# M5_Stick_LocoNet_Interface_2021-01-25.net
KiCad netlist of a schematic drawn in EasyEDA
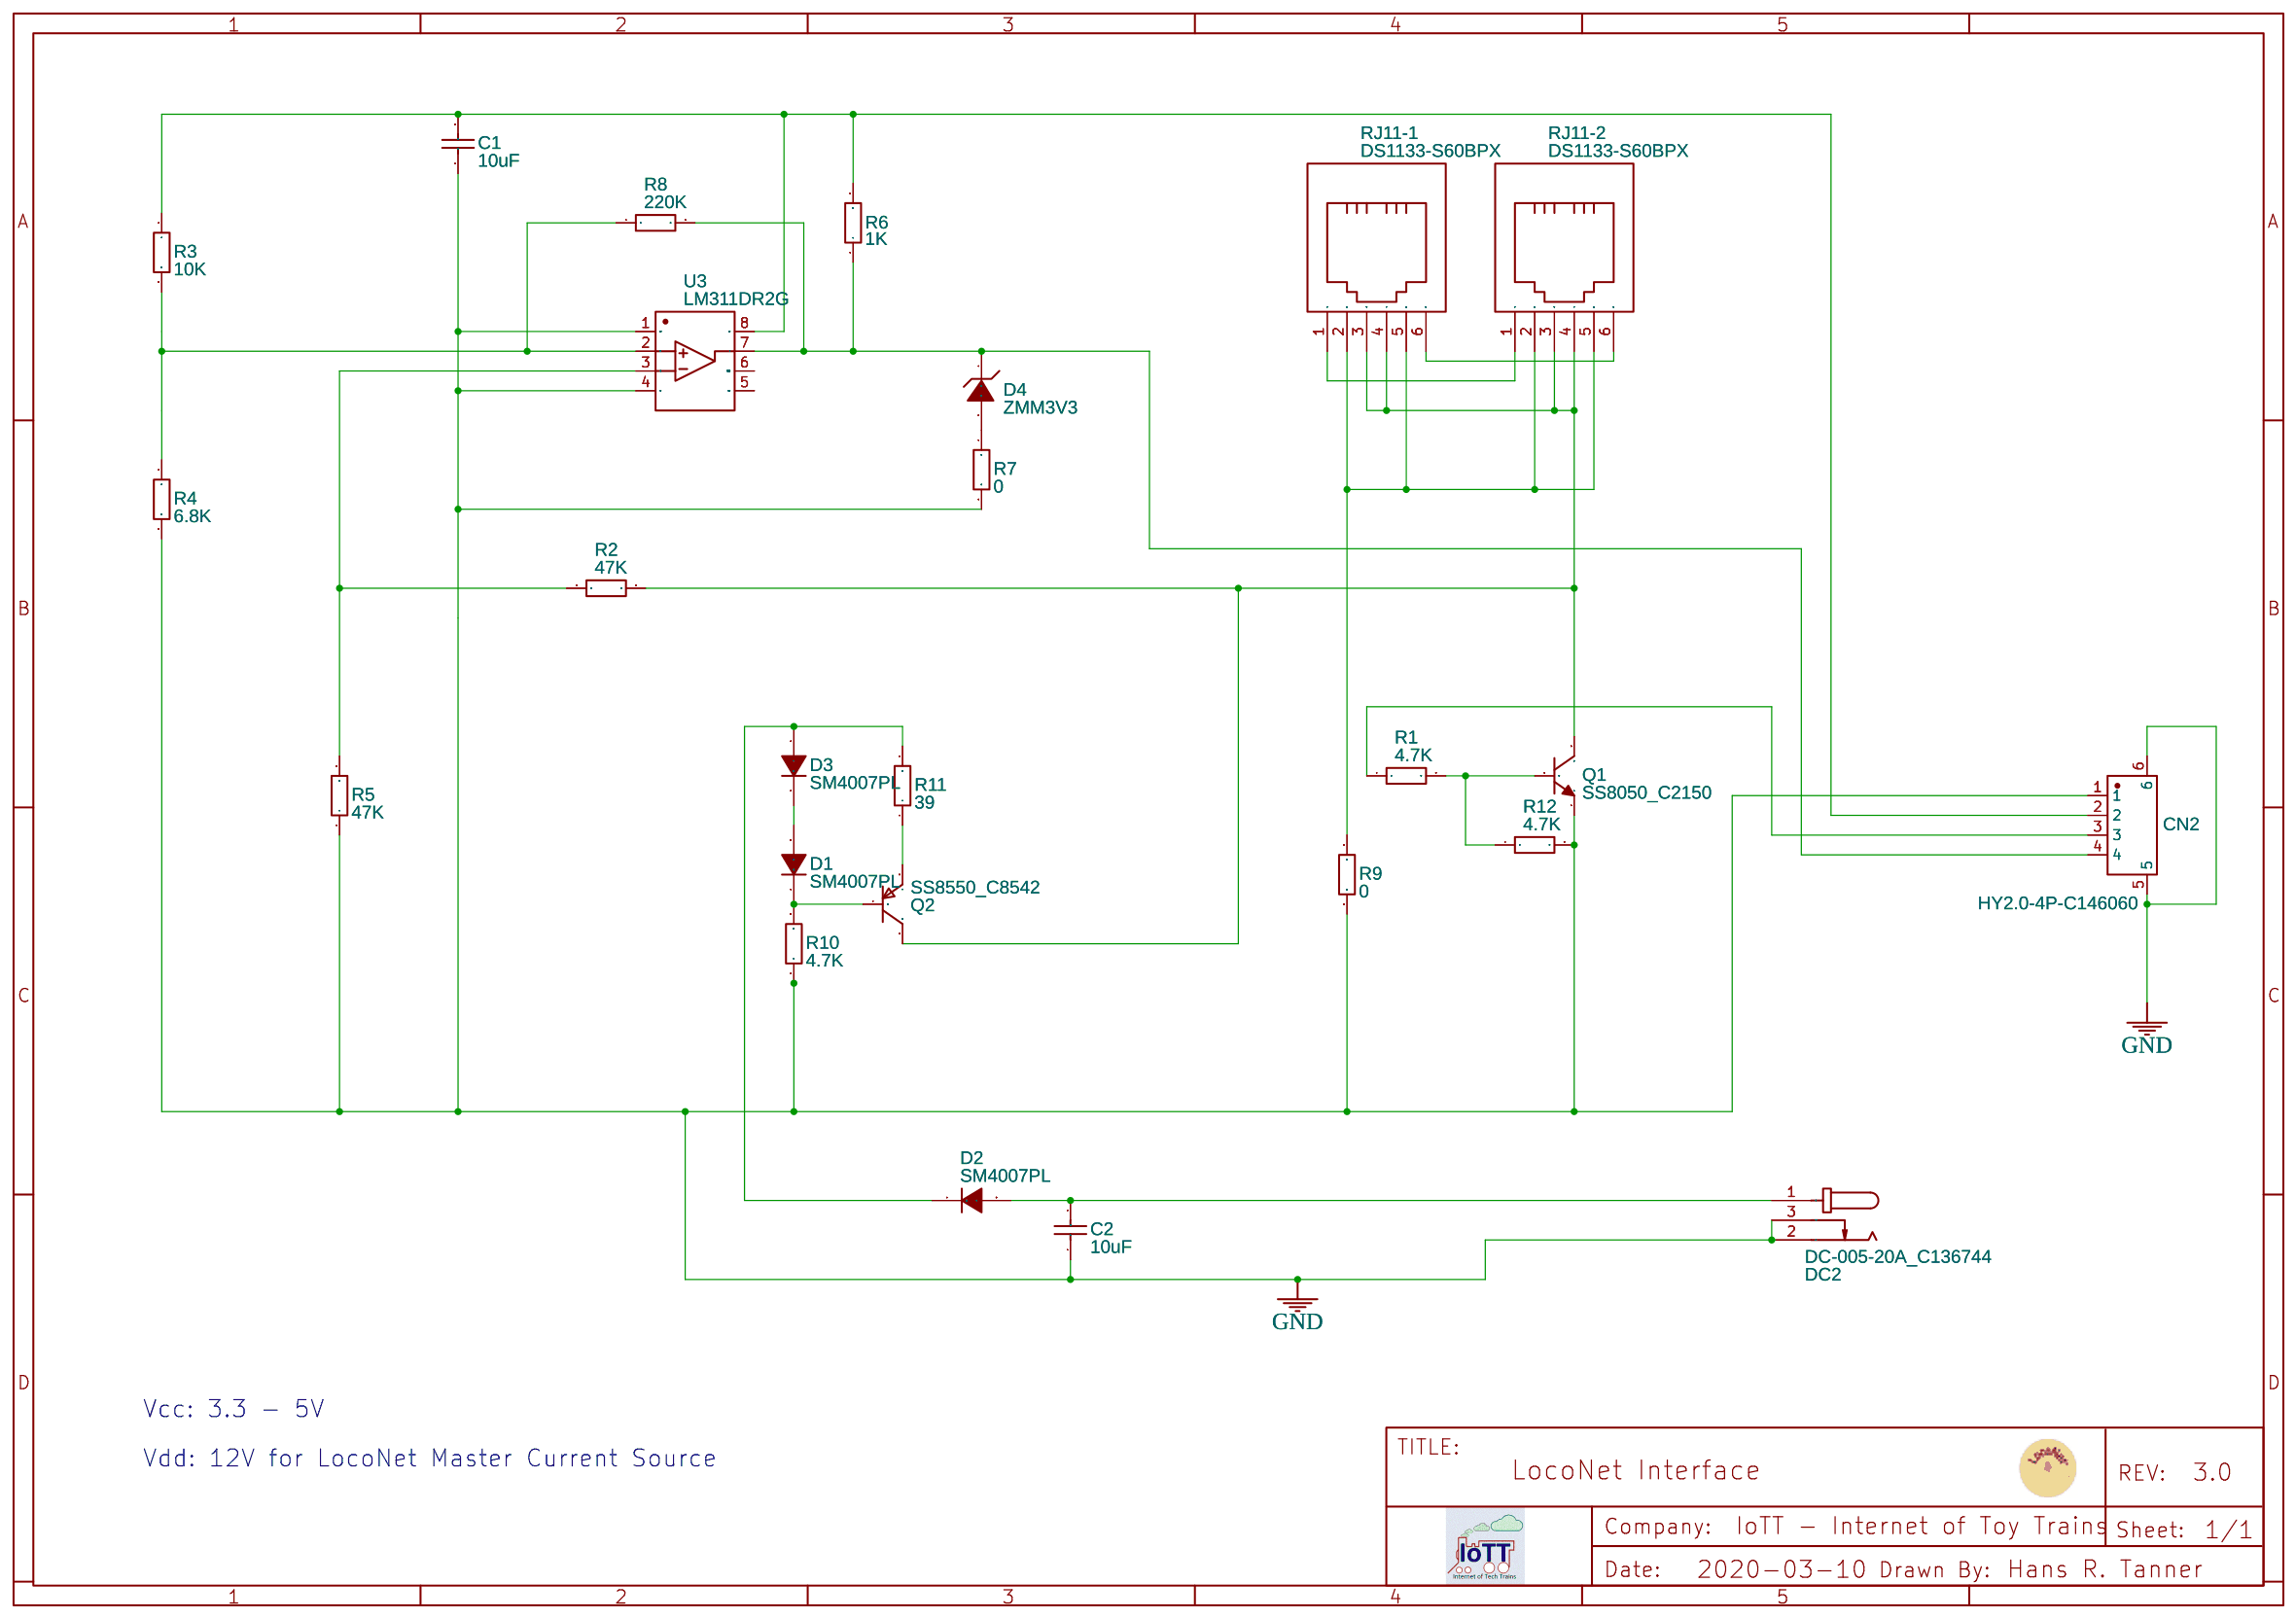
[diagram p0: schematic sheet]

(export (version "E")
  (design (tool "Eeschema 10.0.6"))
  (components
    (comp (ref "C1")
      (value "10uF")
      (fields
        (field (name "BOM_Manufacturer Part") "CL21A106KAYNNNE")
        (field (name "BOM_Supplier Part") "C15850")
      )
      (libsource (lib "") (part "CL21A106KAYNNNE"))
    )
    (comp (ref "C2")
      (value "10uF")
      (fields
        (field (name "BOM_Manufacturer Part") "CL21A106KAYNNNE")
        (field (name "BOM_Supplier Part") "C15850")
      )
      (libsource (lib "") (part "CL21A106KAYNNNE"))
    )
    (comp (ref "CN2")
      (value "HY2.0-4P-C146060")
      (fields (field (name "BOM_Supplier Part") "C146060"))
      (libsource (lib "") (part "HY2.0-4P-C146060"))
    )
    (comp (ref "D1")
      (value "SM4007PL")
      (fields (field (name "BOM_Supplier Part") "C64898"))
      (libsource (lib "") (part "SM4007PL"))
    )
    (comp (ref "D2")
      (value "SM4007PL")
      (fields (field (name "BOM_Supplier Part") "C64898"))
      (libsource (lib "") (part "SM4007PL_1"))
    )
    (comp (ref "D3")
      (value "SM4007PL")
      (fields (field (name "BOM_Supplier Part") "C64898"))
      (libsource (lib "") (part "SM4007PL"))
    )
    (comp (ref "D4")
      (value "ZMM3V3")
      (fields (field (name "BOM_Supplier Part") "C8056"))
      (libsource (lib "") (part "ZMM3V3"))
    )
    (comp (ref "DC2")
      (value "DC-005-20A_C136744")
      (fields
        (field (name "BOM_Manufacturer Part") "DC-005-20A")
        (field (name "BOM_Supplier Part") "C136744")
      )
      (libsource (lib "") (part "DC-005-20A_C136744"))
    )
    (comp (ref "Q1")
      (value "SS8050_C2150")
      (fields (field (name "BOM_Manufacturer Part") "SS8050") (field (name "BOM_Supplier Part") "C2150"))
      (libsource (lib "") (part "SS8050_C2150"))
    )
    (comp (ref "Q2")
      (value "SS8550_C8542")
      (fields (field (name "BOM_Manufacturer Part") "SS8550") (field (name "BOM_Supplier Part") "C8542"))
      (libsource (lib "") (part "SS8550_C8542"))
    )
    (comp (ref "R1")
      (value "4.7K")
      (fields
        (field (name "BOM_Manufacturer Part") "0603WAF4701T5E")
        (field (name "BOM_Supplier Part") "C23162")
      )
      (libsource (lib "") (part "0603WAF4701T5E_1"))
    )
    (comp (ref "R2")
      (value "47K")
      (fields
        (field (name "BOM_Manufacturer Part") "0603WAF4702T5E")
        (field (name "BOM_Supplier Part") "C25819")
      )
      (libsource (lib "") (part "0603WAF4702T5E_1"))
    )
    (comp (ref "R3")
      (value "10K")
      (fields
        (field (name "BOM_Manufacturer Part") "0603WAF1002T5E")
        (field (name "BOM_Supplier Part") "C25804")
      )
      (libsource (lib "") (part "0603WAF1002T5E"))
    )
    (comp (ref "R4")
      (value "6.8K")
      (fields
        (field (name "BOM_Manufacturer Part") "0603WAF6801T5E")
        (field (name "BOM_Supplier Part") "C23212")
      )
      (libsource (lib "") (part "0603WAF6801T5E"))
    )
    (comp (ref "R5")
      (value "47K")
      (fields
        (field (name "BOM_Manufacturer Part") "0603WAF4702T5E")
        (field (name "BOM_Supplier Part") "C25819")
      )
      (libsource (lib "") (part "0603WAF4702T5E"))
    )
    (comp (ref "R6")
      (value "1K")
      (fields
        (field (name "BOM_Manufacturer Part") "0402WGF1001TCE")
        (field (name "BOM_Supplier Part") "C11702")
      )
      (libsource (lib "") (part "0402WGF1001TCE"))
    )
    (comp (ref "R7")
      (value "0")
      (fields
        (field (name "BOM_Manufacturer Part") "0402WGF0000TCE")
        (field (name "BOM_Supplier Part") "C17168")
      )
      (libsource (lib "") (part "0402WGF0000TCE"))
    )
    (comp (ref "R8")
      (value "220K")
      (fields
        (field (name "BOM_Manufacturer Part") "0603WAF2203T5E")
        (field (name "BOM_Supplier Part") "C22961")
      )
      (libsource (lib "") (part "0603WAF2203T5E"))
    )
    (comp (ref "R9")
      (value "0")
      (fields
        (field (name "BOM_Manufacturer Part") "0402WGF0000TCE")
        (field (name "BOM_Supplier Part") "C17168")
      )
      (libsource (lib "") (part "0402WGF0000TCE"))
    )
    (comp (ref "R10")
      (value "4.7K")
      (fields
        (field (name "BOM_Manufacturer Part") "0603WAF4701T5E")
        (field (name "BOM_Supplier Part") "C23162")
      )
      (libsource (lib "") (part "0603WAF4701T5E"))
    )
    (comp (ref "R11")
      (value "39")
      (fields
        (field (name "BOM_Manufacturer Part") "TC0325B390JT5E")
        (field (name "BOM_Supplier Part") "C146566")
      )
      (libsource (lib "") (part "TC0325B390JT5E"))
    )
    (comp (ref "R12")
      (value "4.7K")
      (fields
        (field (name "BOM_Manufacturer Part") "0603WAF4701T5E")
        (field (name "BOM_Supplier Part") "C23162")
      )
      (libsource (lib "") (part "0603WAF4701T5E_1"))
    )
    (comp (ref "RJ11-1")
      (value "DS1133-S60BPX")
      (fields (field (name "BOM_Supplier Part") "C77859"))
      (libsource (lib "") (part "Unknown_690_-680"))
    )
    (comp (ref "RJ11-2")
      (value "DS1133-S60BPX")
      (fields (field (name "BOM_Supplier Part") "C77859"))
      (libsource (lib "") (part "Unknown_785_-680"))
    )
    (comp (ref "U3")
      (value "LM311DR2G")
      (fields (field (name "BOM_Supplier Part") "C231850"))
      (libsource (lib "") (part "LM311DR2G"))
    )
  )
  (nets
    (net (code "1") (name "GND") (class "Default")
      (node (ref "C1") (pin "1") (pinfunction "1_1") (pintype "input"))
      (node (ref "C2") (pin "1") (pinfunction "1_1") (pintype "input"))
      (node (ref "CN2") (pin "1") (pinfunction "1_1") (pintype "unspecified"))
      (node (ref "CN2") (pin "5") (pinfunction "5_5") (pintype "unspecified"))
      (node (ref "CN2") (pin "6") (pinfunction "6_6") (pintype "unspecified"))
      (node (ref "DC2") (pin "2") (pinfunction "2_2") (pintype "unspecified"))
      (node (ref "DC2") (pin "3") (pinfunction "3_3") (pintype "unspecified"))
      (node (ref "Q1") (pin "2") (pinfunction "E_2") (pintype "unspecified"))
      (node (ref "R10") (pin "1") (pinfunction "1_1") (pintype "input"))
      (node (ref "R12") (pin "2") (pinfunction "2_2") (pintype "input"))
      (node (ref "R4") (pin "2") (pinfunction "2_2") (pintype "input"))
      (node (ref "R5") (pin "1") (pinfunction "1_1") (pintype "input"))
      (node (ref "R7") (pin "2") (pinfunction "2_2") (pintype "input"))
      (node (ref "R9") (pin "2") (pinfunction "2_2") (pintype "input"))
      (node (ref "U3") (pin "1") (pinfunction "GND_1") (pintype "unspecified"))
      (node (ref "U3") (pin "4") (pinfunction "VEE_4") (pintype "unspecified"))
    )
    (net (code "2") (name "Net-(CN2-Pad3)") (class "Default")
      (node (ref "CN2") (pin "3") (pinfunction "3_3") (pintype "unspecified"))
      (node (ref "R1") (pin "1") (pinfunction "1_1") (pintype "input"))
    )
    (net (code "3") (name "Net-(D1-A)") (class "Default")
      (node (ref "D1") (pin "2") (pinfunction "A_2") (pintype "unspecified"))
      (node (ref "D3") (pin "1") (pinfunction "C_1") (pintype "unspecified"))
    )
    (net (code "4") (name "Net-(D1-C)") (class "Default")
      (node (ref "D1") (pin "1") (pinfunction "C_1") (pintype "unspecified"))
      (node (ref "Q2") (pin "1") (pinfunction "B_1") (pintype "unspecified"))
      (node (ref "R10") (pin "2") (pinfunction "2_2") (pintype "input"))
    )
    (net (code "5") (name "Net-(D2-A)") (class "Default")
      (node (ref "C2") (pin "2") (pinfunction "2_2") (pintype "input"))
      (node (ref "D2") (pin "2") (pinfunction "A_2") (pintype "unspecified"))
      (node (ref "DC2") (pin "1") (pinfunction "1_1") (pintype "unspecified"))
    )
    (net (code "6") (name "Net-(D2-C)") (class "Default")
      (node (ref "D2") (pin "1") (pinfunction "C_1") (pintype "unspecified"))
      (node (ref "D3") (pin "2") (pinfunction "A_2") (pintype "unspecified"))
      (node (ref "R11") (pin "2") (pinfunction "2_2") (pintype "input"))
    )
    (net (code "7") (name "Net-(D4-A)") (class "Default")
      (node (ref "D4") (pin "2") (pinfunction "A_2") (pintype "unspecified"))
      (node (ref "R7") (pin "1") (pinfunction "1_1") (pintype "input"))
    )
    (net (code "8") (name "Net-(D4-C)") (class "Default")
      (node (ref "CN2") (pin "4") (pinfunction "4_4") (pintype "unspecified"))
      (node (ref "D4") (pin "1") (pinfunction "C_1") (pintype "unspecified"))
      (node (ref "R6") (pin "1") (pinfunction "1_1") (pintype "input"))
      (node (ref "R8") (pin "2") (pinfunction "2_2") (pintype "input"))
      (node (ref "U3") (pin "7") (pinfunction "7_7") (pintype "unspecified"))
    )
    (net (code "9") (name "Net-(Q1-B)") (class "Default")
      (node (ref "Q1") (pin "1") (pinfunction "B_1") (pintype "unspecified"))
      (node (ref "R1") (pin "2") (pinfunction "2_2") (pintype "input"))
      (node (ref "R12") (pin "1") (pinfunction "1_1") (pintype "input"))
    )
    (net (code "10") (name "Net-(Q1-C)") (class "Default")
      (node (ref "Q1") (pin "3") (pinfunction "C_3") (pintype "unspecified"))
      (node (ref "Q2") (pin "3") (pinfunction "C_3") (pintype "unspecified"))
      (node (ref "R2") (pin "2") (pinfunction "2_2") (pintype "input"))
      (node (ref "RJ11-1") (pin "3") (pinfunction "3_3") (pintype "unspecified"))
      (node (ref "RJ11-1") (pin "4") (pinfunction "4_4") (pintype "unspecified"))
      (node (ref "RJ11-2") (pin "3") (pinfunction "3_3") (pintype "unspecified"))
      (node (ref "RJ11-2") (pin "4") (pinfunction "4_4") (pintype "unspecified"))
    )
    (net (code "11") (name "Net-(Q2-E)") (class "Default")
      (node (ref "Q2") (pin "2") (pinfunction "E_2") (pintype "unspecified"))
      (node (ref "R11") (pin "1") (pinfunction "1_1") (pintype "input"))
    )
    (net (code "12") (name "Net-(R2-Pad1)") (class "Default")
      (node (ref "R2") (pin "1") (pinfunction "1_1") (pintype "input"))
      (node (ref "R5") (pin "2") (pinfunction "2_2") (pintype "input"))
      (node (ref "U3") (pin "3") (pinfunction "3_3") (pintype "unspecified"))
    )
    (net (code "13") (name "Net-(R3-Pad2)") (class "Default")
      (node (ref "R3") (pin "2") (pinfunction "2_2") (pintype "input"))
      (node (ref "R4") (pin "1") (pinfunction "1_1") (pintype "input"))
      (node (ref "R8") (pin "1") (pinfunction "1_1") (pintype "input"))
      (node (ref "U3") (pin "2") (pinfunction "2_2") (pintype "unspecified"))
    )
    (net (code "14") (name "Net-(R9-Pad1)") (class "Default")
      (node (ref "R9") (pin "1") (pinfunction "1_1") (pintype "input"))
      (node (ref "RJ11-1") (pin "2") (pinfunction "2_2") (pintype "unspecified"))
      (node (ref "RJ11-1") (pin "5") (pinfunction "5_5") (pintype "unspecified"))
      (node (ref "RJ11-2") (pin "2") (pinfunction "2_2") (pintype "unspecified"))
      (node (ref "RJ11-2") (pin "5") (pinfunction "5_5") (pintype "unspecified"))
    )
    (net (code "15") (name "Net-(RJ11-1-Pad1)") (class "Default")
      (node (ref "RJ11-1") (pin "1") (pinfunction "1_1") (pintype "unspecified"))
      (node (ref "RJ11-2") (pin "1") (pinfunction "1_1") (pintype "unspecified"))
    )
    (net (code "16") (name "Net-(RJ11-1-Pad6)") (class "Default")
      (node (ref "RJ11-1") (pin "6") (pinfunction "6_6") (pintype "unspecified"))
      (node (ref "RJ11-2") (pin "6") (pinfunction "6_6") (pintype "unspecified"))
    )
    (net (code "17") (name "Net-(U3-VCC)") (class "Default")
      (node (ref "C1") (pin "2") (pinfunction "2_2") (pintype "input"))
      (node (ref "CN2") (pin "2") (pinfunction "2_2") (pintype "unspecified"))
      (node (ref "R3") (pin "1") (pinfunction "1_1") (pintype "input"))
      (node (ref "R6") (pin "2") (pinfunction "2_2") (pintype "input"))
      (node (ref "U3") (pin "8") (pinfunction "VCC_8") (pintype "unspecified"))
    )
    (net (code "18") (name "unconnected-(U3-BALANCE-Pad5)") (class "Default")
      (node (ref "U3") (pin "5") (pinfunction "BALANCE_5") (pintype "unspecified"))
    )
    (net (code "19") (name "unconnected-(U3-BALANCE{slash}STROBE-Pad6)") (class "Default")
      (node (ref "U3") (pin "6") (pinfunction "BALANCE/STROBE_6") (pintype "unspecified"))
    )
  )
)
